# bt-snes-aa-ncp1402-letter-select-attiny2.net
KiCad netlist of a schematic drawn in EAGLE
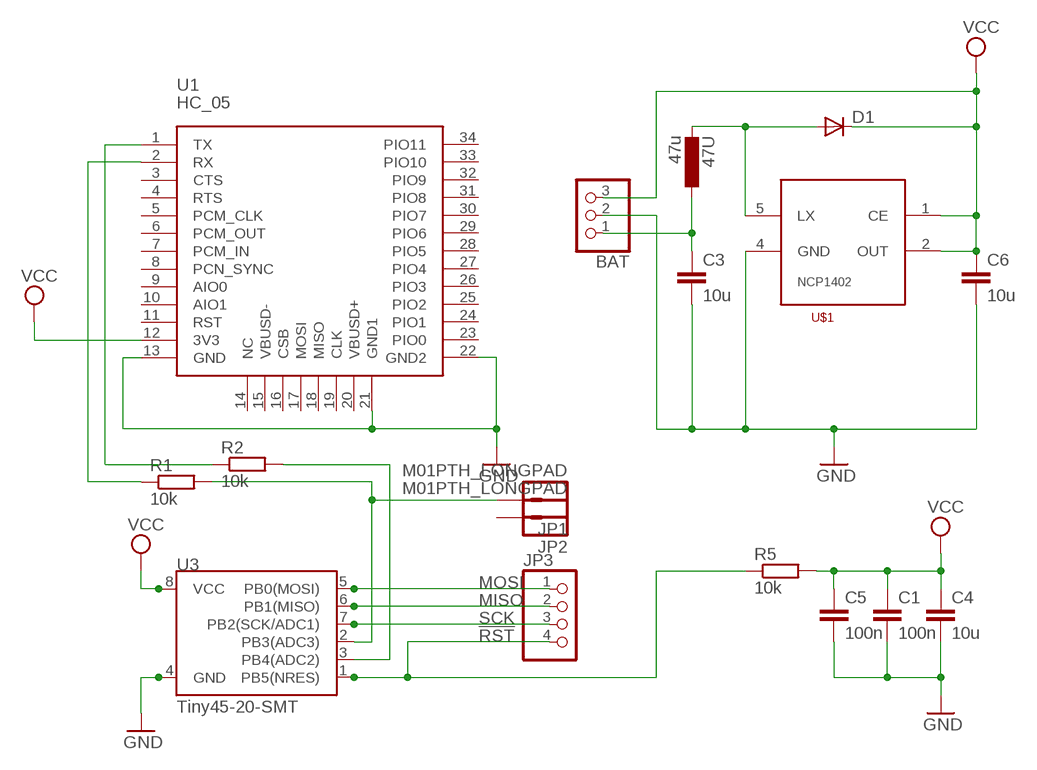
[diagram p0: schematic, sheet 1]

(export (version "E")
  (design (tool "Eeschema 10.0.6"))
  (components
    (comp (ref "47U")
      (value "47u")
      (footprint "eagle-import:C1210")
      (libsource (lib "eagle-import") (part "L-EUL1210"))
    )
    (comp (ref "BAT")
      (value "PINHD-1X3")
      (footprint "eagle-import:1X03")
      (libsource (lib "eagle-import") (part "PINHD-1X3"))
    )
    (comp (ref "C1")
      (value "100n")
      (footprint "eagle-import:C0805K")
      (libsource (lib "eagle-import") (part "C-EUC0805K"))
    )
    (comp (ref "C3")
      (value "10u")
      (footprint "eagle-import:C0805K")
      (libsource (lib "eagle-import") (part "C-EUC0805K"))
    )
    (comp (ref "C4")
      (value "10u")
      (footprint "eagle-import:C0805K")
      (libsource (lib "eagle-import") (part "C-EUC0805K"))
    )
    (comp (ref "C5")
      (value "100n")
      (footprint "eagle-import:C0805K")
      (libsource (lib "eagle-import") (part "C-EUC0805K"))
    )
    (comp (ref "C6")
      (value "10u")
      (footprint "eagle-import:C0805K")
      (libsource (lib "eagle-import") (part "C-EUC0805K"))
    )
    (comp (ref "D1")
      (value "DIODE-SOD80C")
      (footprint "eagle-import:SOD80C")
      (libsource (lib "eagle-import") (part "DIODE-SOD80C"))
    )
    (comp (ref "JP1")
      (value "M01PTH_LONGPAD")
      (footprint "eagle-import:1X01_LONGPAD")
      (libsource (lib "eagle-import") (part "M01PTH_LONGPAD"))
    )
    (comp (ref "JP2")
      (value "M01PTH_LONGPAD")
      (footprint "eagle-import:1X01_LONGPAD")
      (libsource (lib "eagle-import") (part "M01PTH_LONGPAD"))
    )
    (comp (ref "JP3")
      (value "PINHD-1X4")
      (footprint "eagle-import:1X04")
      (libsource (lib "eagle-import") (part "PINHD-1X4"))
    )
    (comp (ref "R1")
      (value "10k")
      (footprint "eagle-import:M0805")
      (libsource (lib "eagle-import") (part "R-EU_M0805"))
    )
    (comp (ref "R2")
      (value "10k")
      (footprint "eagle-import:M0805")
      (libsource (lib "eagle-import") (part "R-EU_M0805"))
    )
    (comp (ref "R5")
      (value "10k")
      (footprint "eagle-import:M0805")
      (libsource (lib "eagle-import") (part "R-EU_M0805"))
    )
    (comp (ref "U$1")
      (value "NCP1402-SOT23-5")
      (footprint "eagle-import:SOT23-5")
      (libsource (lib "eagle-import") (part "NCP1402-SOT23-5"))
    )
    (comp (ref "U1")
      (value "HC_05")
      (footprint "eagle-import:BLUETOOTH_SMD")
      (libsource (lib "eagle-import") (part "HC_05"))
    )
    (comp (ref "U3")
      (value "Tiny45-20-SMT")
      (footprint "eagle-import:SO08-EIAJ")
      (libsource (lib "eagle-import") (part "ATTINY45TINY45-20-SMT"))
    )
  )
  (nets
    (net (code "1") (name "/MISO") (class "Default")
      (node (ref "JP3") (pin "2") (pinfunction "2_2") (pintype "passive"))
      (node (ref "U3") (pin "6") (pinfunction "PB1(MISO)_6") (pintype "bidirectional"))
    )
    (net (code "2") (name "/MOSI") (class "Default")
      (node (ref "JP3") (pin "1") (pinfunction "1_1") (pintype "passive"))
      (node (ref "U3") (pin "5") (pinfunction "PB0(MOSI)_5") (pintype "bidirectional"))
    )
    (net (code "3") (name "/SCK") (class "Default")
      (node (ref "JP3") (pin "3") (pinfunction "3_3") (pintype "passive"))
      (node (ref "U3") (pin "7") (pinfunction "PB2(SCK/ADC1)_7") (pintype "bidirectional"))
    )
    (net (code "4") (name "/~{RST}") (class "Default")
      (node (ref "JP3") (pin "4") (pinfunction "4_4") (pintype "passive"))
      (node (ref "R5") (pin "1") (pinfunction "1_1") (pintype "passive"))
      (node (ref "U3") (pin "1") (pinfunction "PB5(NRES)_1") (pintype "bidirectional"))
    )
    (net (code "5") (name "GND") (class "Default")
      (node (ref "BAT") (pin "2") (pinfunction "2_2") (pintype "passive"))
      (node (ref "C1") (pin "2") (pinfunction "2_2") (pintype "passive"))
      (node (ref "C3") (pin "2") (pinfunction "2_2") (pintype "passive"))
      (node (ref "C4") (pin "2") (pinfunction "2_2") (pintype "passive"))
      (node (ref "C5") (pin "2") (pinfunction "2_2") (pintype "passive"))
      (node (ref "C6") (pin "2") (pinfunction "2_2") (pintype "passive"))
      (node (ref "U$1") (pin "4") (pinfunction "GND_4") (pintype "bidirectional"))
      (node (ref "U1") (pin "13") (pinfunction "GND_13") (pintype "bidirectional"))
      (node (ref "U1") (pin "21") (pinfunction "GND1_21") (pintype "bidirectional"))
      (node (ref "U1") (pin "22") (pinfunction "GND2_22") (pintype "bidirectional"))
      (node (ref "U3") (pin "4") (pinfunction "GND_4") (pintype "bidirectional"))
    )
    (net (code "6") (name "Net-(47U-Pad1)") (class "Default")
      (node (ref "47U") (pin "1") (pinfunction "1_1") (pintype "passive"))
      (node (ref "BAT") (pin "1") (pinfunction "1_1") (pintype "passive"))
      (node (ref "C3") (pin "1") (pinfunction "1_1") (pintype "passive"))
    )
    (net (code "7") (name "Net-(U$1-LX)") (class "Default")
      (node (ref "47U") (pin "2") (pinfunction "2_2") (pintype "passive"))
      (node (ref "D1") (pin "A") (pinfunction "A_A") (pintype "passive"))
      (node (ref "U$1") (pin "5") (pinfunction "LX_5") (pintype "bidirectional"))
    )
    (net (code "8") (name "Net-(U1-RX)") (class "Default")
      (node (ref "R1") (pin "1") (pinfunction "1_1") (pintype "passive"))
      (node (ref "U1") (pin "2") (pinfunction "RX_2") (pintype "bidirectional"))
    )
    (net (code "9") (name "Net-(U1-TX)") (class "Default")
      (node (ref "R2") (pin "1") (pinfunction "1_1") (pintype "passive"))
      (node (ref "U1") (pin "1") (pinfunction "TX_1") (pintype "bidirectional"))
    )
    (net (code "10") (name "Net-(U3-PB3(ADC3))") (class "Default")
      (node (ref "JP1") (pin "1") (pinfunction "1_1") (pintype "passive"))
      (node (ref "R1") (pin "2") (pinfunction "2_2") (pintype "passive"))
      (node (ref "U3") (pin "2") (pinfunction "PB3(ADC3)_2") (pintype "bidirectional"))
    )
    (net (code "11") (name "Net-(U3-PB4(ADC2))") (class "Default")
      (node (ref "R2") (pin "2") (pinfunction "2_2") (pintype "passive"))
      (node (ref "U3") (pin "3") (pinfunction "PB4(ADC2)_3") (pintype "bidirectional"))
    )
    (net (code "12") (name "VCC") (class "Default")
      (node (ref "BAT") (pin "3") (pinfunction "3_3") (pintype "passive"))
      (node (ref "C1") (pin "1") (pinfunction "1_1") (pintype "passive"))
      (node (ref "C4") (pin "1") (pinfunction "1_1") (pintype "passive"))
      (node (ref "C5") (pin "1") (pinfunction "1_1") (pintype "passive"))
      (node (ref "C6") (pin "1") (pinfunction "1_1") (pintype "passive"))
      (node (ref "D1") (pin "C") (pinfunction "C_C") (pintype "passive"))
      (node (ref "R5") (pin "2") (pinfunction "2_2") (pintype "passive"))
      (node (ref "U$1") (pin "1") (pinfunction "CE_1") (pintype "bidirectional"))
      (node (ref "U$1") (pin "2") (pinfunction "OUT_2") (pintype "bidirectional"))
      (node (ref "U1") (pin "12") (pinfunction "3V3_12") (pintype "bidirectional"))
      (node (ref "U3") (pin "8") (pinfunction "VCC_8") (pintype "bidirectional"))
    )
    (net (code "13") (name "unconnected-(JP2-Pad1)") (class "Default")
      (node (ref "JP2") (pin "1") (pinfunction "1_1") (pintype "passive"))
    )
    (net (code "14") (name "unconnected-(U1-AIO0-Pad9)") (class "Default")
      (node (ref "U1") (pin "9") (pinfunction "AIO0_9") (pintype "bidirectional"))
    )
    (net (code "15") (name "unconnected-(U1-AIO1-Pad10)") (class "Default")
      (node (ref "U1") (pin "10") (pinfunction "AIO1_10") (pintype "bidirectional"))
    )
    (net (code "16") (name "unconnected-(U1-CLK-Pad19)") (class "Default")
      (node (ref "U1") (pin "19") (pinfunction "CLK_19") (pintype "bidirectional"))
    )
    (net (code "17") (name "unconnected-(U1-CSB-Pad16)") (class "Default")
      (node (ref "U1") (pin "16") (pinfunction "CSB_16") (pintype "bidirectional"))
    )
    (net (code "18") (name "unconnected-(U1-CTS-Pad3)") (class "Default")
      (node (ref "U1") (pin "3") (pinfunction "CTS_3") (pintype "bidirectional"))
    )
    (net (code "19") (name "unconnected-(U1-MISO-Pad18)") (class "Default")
      (node (ref "U1") (pin "18") (pinfunction "MISO_18") (pintype "bidirectional"))
    )
    (net (code "20") (name "unconnected-(U1-MOSI-Pad17)") (class "Default")
      (node (ref "U1") (pin "17") (pinfunction "MOSI_17") (pintype "bidirectional"))
    )
    (net (code "21") (name "unconnected-(U1-NC-Pad14)") (class "Default")
      (node (ref "U1") (pin "14") (pinfunction "NC_14") (pintype "bidirectional"))
    )
    (net (code "22") (name "unconnected-(U1-PCM_CLK-Pad5)") (class "Default")
      (node (ref "U1") (pin "5") (pinfunction "PCM_CLK_5") (pintype "bidirectional"))
    )
    (net (code "23") (name "unconnected-(U1-PCM_IN-Pad7)") (class "Default")
      (node (ref "U1") (pin "7") (pinfunction "PCM_IN_7") (pintype "bidirectional"))
    )
    (net (code "24") (name "unconnected-(U1-PCM_OUT-Pad6)") (class "Default")
      (node (ref "U1") (pin "6") (pinfunction "PCM_OUT_6") (pintype "bidirectional"))
    )
    (net (code "25") (name "unconnected-(U1-PCN_SYNC-Pad8)") (class "Default")
      (node (ref "U1") (pin "8") (pinfunction "PCN_SYNC_8") (pintype "bidirectional"))
    )
    (net (code "26") (name "unconnected-(U1-PIO0-Pad23)") (class "Default")
      (node (ref "U1") (pin "23") (pinfunction "PIO0_23") (pintype "bidirectional"))
    )
    (net (code "27") (name "unconnected-(U1-PIO1-Pad24)") (class "Default")
      (node (ref "U1") (pin "24") (pinfunction "PIO1_24") (pintype "bidirectional"))
    )
    (net (code "28") (name "unconnected-(U1-PIO2-Pad25)") (class "Default")
      (node (ref "U1") (pin "25") (pinfunction "PIO2_25") (pintype "bidirectional"))
    )
    (net (code "29") (name "unconnected-(U1-PIO3-Pad26)") (class "Default")
      (node (ref "U1") (pin "26") (pinfunction "PIO3_26") (pintype "bidirectional"))
    )
    (net (code "30") (name "unconnected-(U1-PIO4-Pad27)") (class "Default")
      (node (ref "U1") (pin "27") (pinfunction "PIO4_27") (pintype "bidirectional"))
    )
    (net (code "31") (name "unconnected-(U1-PIO5-Pad28)") (class "Default")
      (node (ref "U1") (pin "28") (pinfunction "PIO5_28") (pintype "bidirectional"))
    )
    (net (code "32") (name "unconnected-(U1-PIO6-Pad29)") (class "Default")
      (node (ref "U1") (pin "29") (pinfunction "PIO6_29") (pintype "bidirectional"))
    )
    (net (code "33") (name "unconnected-(U1-PIO7-Pad30)") (class "Default")
      (node (ref "U1") (pin "30") (pinfunction "PIO7_30") (pintype "bidirectional"))
    )
    (net (code "34") (name "unconnected-(U1-PIO8-Pad31)") (class "Default")
      (node (ref "U1") (pin "31") (pinfunction "PIO8_31") (pintype "bidirectional"))
    )
    (net (code "35") (name "unconnected-(U1-PIO9-Pad32)") (class "Default")
      (node (ref "U1") (pin "32") (pinfunction "PIO9_32") (pintype "bidirectional"))
    )
    (net (code "36") (name "unconnected-(U1-PIO10-Pad33)") (class "Default")
      (node (ref "U1") (pin "33") (pinfunction "PIO10_33") (pintype "bidirectional"))
    )
    (net (code "37") (name "unconnected-(U1-PIO11-Pad34)") (class "Default")
      (node (ref "U1") (pin "34") (pinfunction "PIO11_34") (pintype "bidirectional"))
    )
    (net (code "38") (name "unconnected-(U1-RST-Pad11)") (class "Default")
      (node (ref "U1") (pin "11") (pinfunction "RST_11") (pintype "bidirectional"))
    )
    (net (code "39") (name "unconnected-(U1-RTS-Pad4)") (class "Default")
      (node (ref "U1") (pin "4") (pinfunction "RTS_4") (pintype "bidirectional"))
    )
    (net (code "40") (name "unconnected-(U1-VBUSD+-Pad20)") (class "Default")
      (node (ref "U1") (pin "20") (pinfunction "VBUSD+_20") (pintype "bidirectional"))
    )
    (net (code "41") (name "unconnected-(U1-VBUSD--Pad15)") (class "Default")
      (node (ref "U1") (pin "15") (pinfunction "VBUSD-_15") (pintype "bidirectional"))
    )
  )
)
